# sibu-led-board.net
KiCad netlist of a schematic drawn in EAGLE
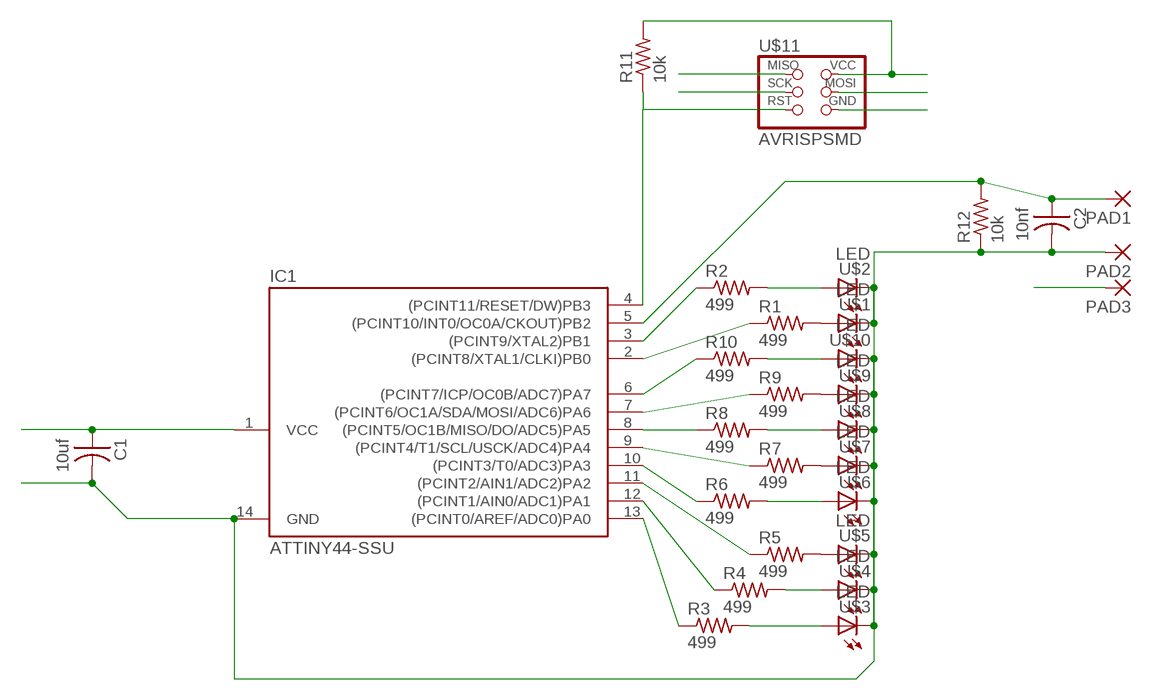
[diagram p0: schematic, sheet 1]

(export (version "E")
  (design (tool "Eeschema 10.0.6"))
  (components
    (comp (ref "C1")
      (value "10uf")
      (footprint "eagle-import:C1206FAB")
      (libsource (lib "eagle-import") (part "CAP-US1206FAB"))
    )
    (comp (ref "C2")
      (value "10nf")
      (footprint "eagle-import:C1206FAB")
      (libsource (lib "eagle-import") (part "CAP-US1206FAB"))
    )
    (comp (ref "IC1")
      (value "ATTINY44-SSU")
      (footprint "eagle-import:SOIC14")
      (libsource (lib "eagle-import") (part "ATTINY44-SSU"))
    )
    (comp (ref "PAD1")
      (value "SMD2")
      (footprint "eagle-import:SMD1,27-2,54")
      (libsource (lib "eagle-import") (part "SMD2"))
    )
    (comp (ref "PAD2")
      (value "SMD2")
      (footprint "eagle-import:SMD1,27-2,54")
      (libsource (lib "eagle-import") (part "SMD2"))
    )
    (comp (ref "PAD3")
      (value "SMD2")
      (footprint "eagle-import:SMD1,27-2,54")
      (libsource (lib "eagle-import") (part "SMD2"))
    )
    (comp (ref "R1")
      (value "499")
      (footprint "eagle-import:R1206FAB")
      (libsource (lib "eagle-import") (part "RES-US1206FAB"))
    )
    (comp (ref "R2")
      (value "499")
      (footprint "eagle-import:R1206FAB")
      (libsource (lib "eagle-import") (part "RES-US1206FAB"))
    )
    (comp (ref "R3")
      (value "499")
      (footprint "eagle-import:R1206FAB")
      (libsource (lib "eagle-import") (part "RES-US1206FAB"))
    )
    (comp (ref "R4")
      (value "499")
      (footprint "eagle-import:R1206FAB")
      (libsource (lib "eagle-import") (part "RES-US1206FAB"))
    )
    (comp (ref "R5")
      (value "499")
      (footprint "eagle-import:R1206FAB")
      (libsource (lib "eagle-import") (part "RES-US1206FAB"))
    )
    (comp (ref "R6")
      (value "499")
      (footprint "eagle-import:R1206FAB")
      (libsource (lib "eagle-import") (part "RES-US1206FAB"))
    )
    (comp (ref "R7")
      (value "499")
      (footprint "eagle-import:R1206FAB")
      (libsource (lib "eagle-import") (part "RES-US1206FAB"))
    )
    (comp (ref "R8")
      (value "499")
      (footprint "eagle-import:R1206FAB")
      (libsource (lib "eagle-import") (part "RES-US1206FAB"))
    )
    (comp (ref "R9")
      (value "499")
      (footprint "eagle-import:R1206FAB")
      (libsource (lib "eagle-import") (part "RES-US1206FAB"))
    )
    (comp (ref "R10")
      (value "499")
      (footprint "eagle-import:R1206FAB")
      (libsource (lib "eagle-import") (part "RES-US1206FAB"))
    )
    (comp (ref "R11")
      (value "10k")
      (footprint "eagle-import:R1206FAB")
      (libsource (lib "eagle-import") (part "RES-US1206FAB"))
    )
    (comp (ref "R12")
      (value "10k")
      (footprint "eagle-import:R1206FAB")
      (libsource (lib "eagle-import") (part "RES-US1206FAB"))
    )
    (comp (ref "U$1")
      (value "LED")
      (footprint "eagle-import:LED1206FAB")
      (libsource (lib "eagle-import") (part "LEDFAB1206"))
    )
    (comp (ref "U$2")
      (value "LED")
      (footprint "eagle-import:LED1206FAB")
      (libsource (lib "eagle-import") (part "LEDFAB1206"))
    )
    (comp (ref "U$3")
      (value "LED")
      (footprint "eagle-import:LED1206FAB")
      (libsource (lib "eagle-import") (part "LEDFAB1206"))
    )
    (comp (ref "U$4")
      (value "LED")
      (footprint "eagle-import:LED1206FAB")
      (libsource (lib "eagle-import") (part "LEDFAB1206"))
    )
    (comp (ref "U$5")
      (value "LED")
      (footprint "eagle-import:LED1206FAB")
      (libsource (lib "eagle-import") (part "LEDFAB1206"))
    )
    (comp (ref "U$6")
      (value "LED")
      (footprint "eagle-import:LED1206FAB")
      (libsource (lib "eagle-import") (part "LEDFAB1206"))
    )
    (comp (ref "U$7")
      (value "LED")
      (footprint "eagle-import:LED1206FAB")
      (libsource (lib "eagle-import") (part "LEDFAB1206"))
    )
    (comp (ref "U$8")
      (value "LED")
      (footprint "eagle-import:LED1206FAB")
      (libsource (lib "eagle-import") (part "LEDFAB1206"))
    )
    (comp (ref "U$9")
      (value "LED")
      (footprint "eagle-import:LED1206FAB")
      (libsource (lib "eagle-import") (part "LEDFAB1206"))
    )
    (comp (ref "U$10")
      (value "LED")
      (footprint "eagle-import:LED1206FAB")
      (libsource (lib "eagle-import") (part "LEDFAB1206"))
    )
    (comp (ref "U$11")
      (value "AVRISPSMD")
      (footprint "eagle-import:2X03SMD")
      (libsource (lib "eagle-import") (part "AVRISPSMD"))
    )
  )
  (nets
    (net (code "1") (name "/GND") (class "Default")
      (node (ref "C1") (pin "2") (pinfunction "2_2") (pintype "passive"))
      (node (ref "C2") (pin "2") (pinfunction "2_2") (pintype "passive"))
      (node (ref "IC1") (pin "14") (pinfunction "GND_14") (pintype "power_in"))
      (node (ref "PAD2") (pin "1") (pinfunction "P_1") (pintype "passive"))
      (node (ref "R12") (pin "1") (pinfunction "1_1") (pintype "passive"))
      (node (ref "U$1") (pin "2") (pinfunction "C_2") (pintype "passive"))
      (node (ref "U$10") (pin "2") (pinfunction "C_2") (pintype "passive"))
      (node (ref "U$11") (pin "6") (pinfunction "GND_6") (pintype "passive"))
      (node (ref "U$2") (pin "2") (pinfunction "C_2") (pintype "passive"))
      (node (ref "U$3") (pin "2") (pinfunction "C_2") (pintype "passive"))
      (node (ref "U$4") (pin "2") (pinfunction "C_2") (pintype "passive"))
      (node (ref "U$5") (pin "2") (pinfunction "C_2") (pintype "passive"))
      (node (ref "U$6") (pin "2") (pinfunction "C_2") (pintype "passive"))
      (node (ref "U$7") (pin "2") (pinfunction "C_2") (pintype "passive"))
      (node (ref "U$8") (pin "2") (pinfunction "C_2") (pintype "passive"))
      (node (ref "U$9") (pin "2") (pinfunction "C_2") (pintype "passive"))
    )
    (net (code "2") (name "/MISO") (class "Default")
      (node (ref "IC1") (pin "8") (pinfunction "(PCINT5/OC1B/MISO/DO/ADC5)PA5_8") (pintype "bidirectional"))
      (node (ref "R8") (pin "1") (pinfunction "1_1") (pintype "passive"))
      (node (ref "U$11") (pin "1") (pinfunction "MISO_1") (pintype "passive"))
    )
    (net (code "3") (name "/MOSI") (class "Default")
      (node (ref "IC1") (pin "7") (pinfunction "(PCINT6/OC1A/SDA/MOSI/ADC6)PA6_7") (pintype "bidirectional"))
      (node (ref "R9") (pin "1") (pinfunction "1_1") (pintype "passive"))
      (node (ref "U$11") (pin "4") (pinfunction "MOSI_4") (pintype "passive"))
    )
    (net (code "4") (name "/SCK") (class "Default")
      (node (ref "IC1") (pin "9") (pinfunction "(PCINT4/T1/SCL/USCK/ADC4)PA4_9") (pintype "bidirectional"))
      (node (ref "R7") (pin "1") (pinfunction "1_1") (pintype "passive"))
      (node (ref "U$11") (pin "3") (pinfunction "SCK_3") (pintype "passive"))
    )
    (net (code "5") (name "/VCC") (class "Default")
      (node (ref "C1") (pin "1") (pinfunction "1_1") (pintype "passive"))
      (node (ref "IC1") (pin "1") (pinfunction "VCC_1") (pintype "power_in"))
      (node (ref "PAD3") (pin "1") (pinfunction "P_1") (pintype "passive"))
      (node (ref "R11") (pin "2") (pinfunction "2_2") (pintype "passive"))
      (node (ref "U$11") (pin "2") (pinfunction "VCC_2") (pintype "passive"))
    )
    (net (code "6") (name "Net-(IC1-(PCINT0{slash}AREF{slash}ADC0)PA0)") (class "Default")
      (node (ref "IC1") (pin "13") (pinfunction "(PCINT0/AREF/ADC0)PA0_13") (pintype "bidirectional"))
      (node (ref "R3") (pin "1") (pinfunction "1_1") (pintype "passive"))
    )
    (net (code "7") (name "Net-(IC1-(PCINT1{slash}AIN0{slash}ADC1)PA1)") (class "Default")
      (node (ref "IC1") (pin "12") (pinfunction "(PCINT1/AIN0/ADC1)PA1_12") (pintype "bidirectional"))
      (node (ref "R4") (pin "1") (pinfunction "1_1") (pintype "passive"))
    )
    (net (code "8") (name "Net-(IC1-(PCINT2{slash}AIN1{slash}ADC2)PA2)") (class "Default")
      (node (ref "IC1") (pin "11") (pinfunction "(PCINT2/AIN1/ADC2)PA2_11") (pintype "bidirectional"))
      (node (ref "R5") (pin "1") (pinfunction "1_1") (pintype "passive"))
    )
    (net (code "9") (name "Net-(IC1-(PCINT3{slash}T0{slash}ADC3)PA3)") (class "Default")
      (node (ref "IC1") (pin "10") (pinfunction "(PCINT3/T0/ADC3)PA3_10") (pintype "bidirectional"))
      (node (ref "R6") (pin "1") (pinfunction "1_1") (pintype "passive"))
    )
    (net (code "10") (name "Net-(IC1-(PCINT7{slash}ICP{slash}OC0B{slash}ADC7)PA7)") (class "Default")
      (node (ref "IC1") (pin "6") (pinfunction "(PCINT7/ICP/OC0B/ADC7)PA7_6") (pintype "bidirectional"))
      (node (ref "R10") (pin "1") (pinfunction "1_1") (pintype "passive"))
    )
    (net (code "11") (name "Net-(IC1-(PCINT8{slash}XTAL1{slash}CLKI)PB0)") (class "Default")
      (node (ref "IC1") (pin "2") (pinfunction "(PCINT8/XTAL1/CLKI)PB0_2") (pintype "bidirectional"))
      (node (ref "R1") (pin "1") (pinfunction "1_1") (pintype "passive"))
    )
    (net (code "12") (name "Net-(IC1-(PCINT9{slash}XTAL2)PB1)") (class "Default")
      (node (ref "IC1") (pin "3") (pinfunction "(PCINT9/XTAL2)PB1_3") (pintype "bidirectional"))
      (node (ref "R2") (pin "1") (pinfunction "1_1") (pintype "passive"))
    )
    (net (code "13") (name "Net-(IC1-(PCINT10{slash}INT0{slash}OC0A{slash}CKOUT)PB2)") (class "Default")
      (node (ref "C2") (pin "1") (pinfunction "1_1") (pintype "passive"))
      (node (ref "IC1") (pin "5") (pinfunction "(PCINT10/INT0/OC0A/CKOUT)PB2_5") (pintype "bidirectional"))
      (node (ref "PAD1") (pin "1") (pinfunction "P_1") (pintype "passive"))
      (node (ref "R12") (pin "2") (pinfunction "2_2") (pintype "passive"))
    )
    (net (code "14") (name "Net-(IC1-(PCINT11{slash}RESET{slash}DW)PB3)") (class "Default")
      (node (ref "IC1") (pin "4") (pinfunction "(PCINT11/RESET/DW)PB3_4") (pintype "bidirectional"))
      (node (ref "R11") (pin "1") (pinfunction "1_1") (pintype "passive"))
      (node (ref "U$11") (pin "5") (pinfunction "RST_5") (pintype "passive"))
    )
    (net (code "15") (name "Net-(U$1-A)") (class "Default")
      (node (ref "R1") (pin "2") (pinfunction "2_2") (pintype "passive"))
      (node (ref "U$1") (pin "1") (pinfunction "A_1") (pintype "passive"))
    )
    (net (code "16") (name "Net-(U$2-A)") (class "Default")
      (node (ref "R2") (pin "2") (pinfunction "2_2") (pintype "passive"))
      (node (ref "U$2") (pin "1") (pinfunction "A_1") (pintype "passive"))
    )
    (net (code "17") (name "Net-(U$3-A)") (class "Default")
      (node (ref "R3") (pin "2") (pinfunction "2_2") (pintype "passive"))
      (node (ref "U$3") (pin "1") (pinfunction "A_1") (pintype "passive"))
    )
    (net (code "18") (name "Net-(U$4-A)") (class "Default")
      (node (ref "R4") (pin "2") (pinfunction "2_2") (pintype "passive"))
      (node (ref "U$4") (pin "1") (pinfunction "A_1") (pintype "passive"))
    )
    (net (code "19") (name "Net-(U$5-A)") (class "Default")
      (node (ref "R5") (pin "2") (pinfunction "2_2") (pintype "passive"))
      (node (ref "U$5") (pin "1") (pinfunction "A_1") (pintype "passive"))
    )
    (net (code "20") (name "Net-(U$6-A)") (class "Default")
      (node (ref "R6") (pin "2") (pinfunction "2_2") (pintype "passive"))
      (node (ref "U$6") (pin "1") (pinfunction "A_1") (pintype "passive"))
    )
    (net (code "21") (name "Net-(U$7-A)") (class "Default")
      (node (ref "R7") (pin "2") (pinfunction "2_2") (pintype "passive"))
      (node (ref "U$7") (pin "1") (pinfunction "A_1") (pintype "passive"))
    )
    (net (code "22") (name "Net-(U$8-A)") (class "Default")
      (node (ref "R8") (pin "2") (pinfunction "2_2") (pintype "passive"))
      (node (ref "U$8") (pin "1") (pinfunction "A_1") (pintype "passive"))
    )
    (net (code "23") (name "Net-(U$9-A)") (class "Default")
      (node (ref "R9") (pin "2") (pinfunction "2_2") (pintype "passive"))
      (node (ref "U$9") (pin "1") (pinfunction "A_1") (pintype "passive"))
    )
    (net (code "24") (name "Net-(U$10-A)") (class "Default")
      (node (ref "R10") (pin "2") (pinfunction "2_2") (pintype "passive"))
      (node (ref "U$10") (pin "1") (pinfunction "A_1") (pintype "passive"))
    )
  )
)
